# Adafruit_T-Cobbler_Plus-ADC.net
KiCad netlist of a schematic drawn in EAGLE
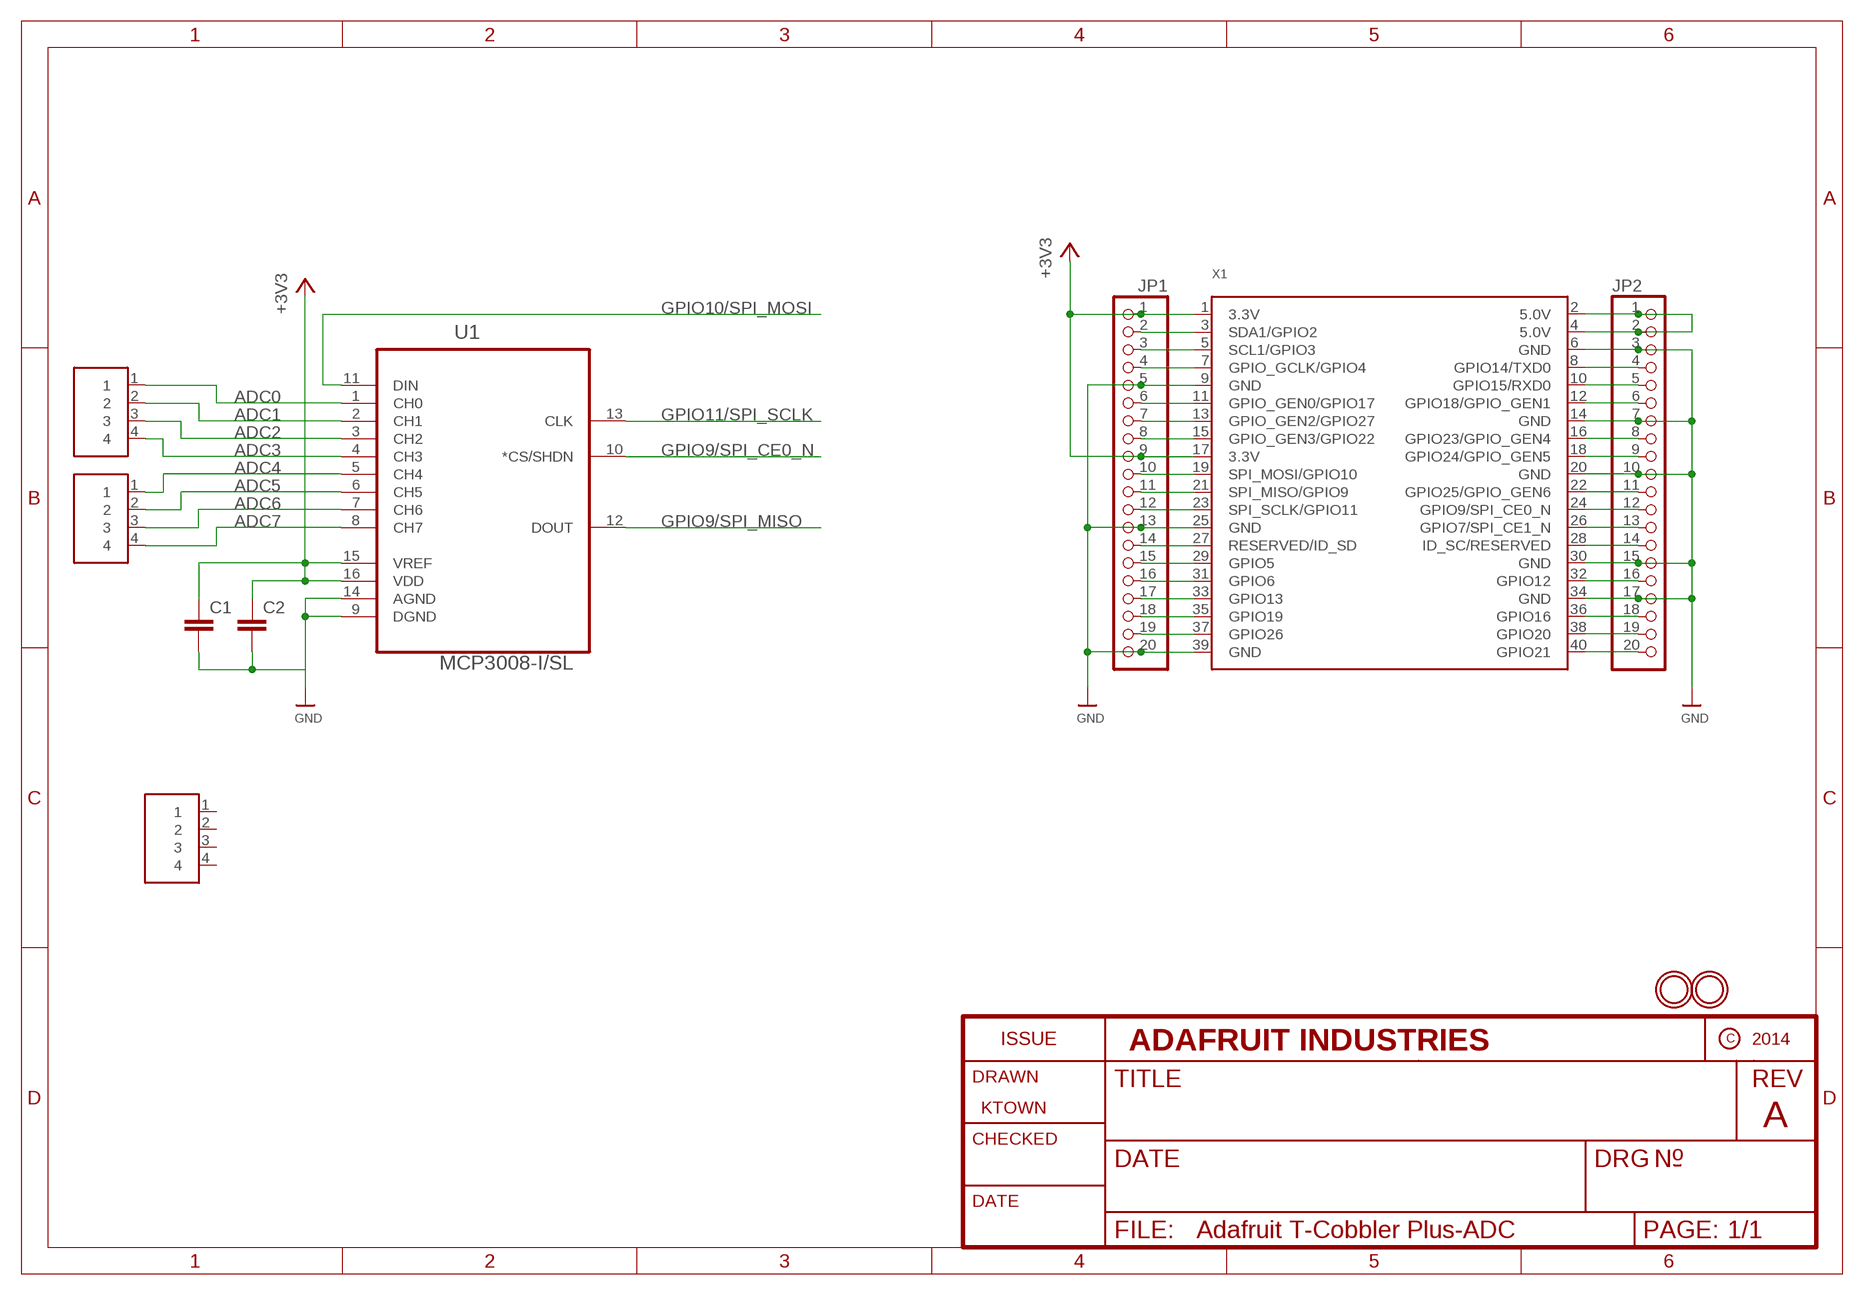
[diagram p0: schematic, sheet 1]

(export (version "E")
  (design (tool "Eeschema 10.0.6"))
  (components
    (comp (ref "C1")
      (value "C-EUC0805")
      (footprint "eagle-import:C0805")
      (libsource (lib "eagle-import") (part "C-EUC0805"))
    )
    (comp (ref "C2")
      (value "C-EUC0805")
      (footprint "eagle-import:C0805")
      (libsource (lib "eagle-import") (part "C-EUC0805"))
    )
    (comp (ref "JP1")
      (value "HEADER-1X20ROUND")
      (footprint "eagle-import:1X20_ROUND")
      (libsource (lib "eagle-import") (part "HEADER-1X20ROUND"))
    )
    (comp (ref "JP2")
      (value "HEADER-1X20ROUND")
      (footprint "eagle-import:1X20_ROUND")
      (libsource (lib "eagle-import") (part "HEADER-1X20ROUND"))
    )
    (comp (ref "U$1")
      (value "1X4THM")
      (footprint "eagle-import:1X4")
      (libsource (lib "eagle-import") (part "1X4THM"))
    )
    (comp (ref "U$2")
      (value "MOUNTINGHOLE2.5_THICK")
      (footprint "eagle-import:MOUNTINGHOLE_2.5_PLATED_THICK")
      (libsource (lib "eagle-import") (part "MOUNTINGHOLE2.5_THICK"))
    )
    (comp (ref "U$4")
      (value "MOUNTINGHOLE2.5_THICK")
      (footprint "eagle-import:MOUNTINGHOLE_2.5_PLATED_THICK")
      (libsource (lib "eagle-import") (part "MOUNTINGHOLE2.5_THICK"))
    )
    (comp (ref "U$9")
      (value "1X4THM")
      (footprint "eagle-import:1X4")
      (libsource (lib "eagle-import") (part "1X4THM"))
    )
    (comp (ref "U$10")
      (value "1X4THM")
      (footprint "eagle-import:1X4")
      (libsource (lib "eagle-import") (part "1X4THM"))
    )
    (comp (ref "U1")
      (value "MCP3008-I/SL")
      (footprint "eagle-import:SOIC127P600X175-16N")
      (libsource (lib "eagle-import") (part "MCP3008-I/SL"))
    )
    (comp (ref "X1")
      (value "RASPBERRYPI_B+_IDC")
      (footprint "eagle-import:RASPBERRYPI_B+_IDC")
      (libsource (lib "eagle-import") (part "RASPBERRYPI_B+_IDC"))
    )
  )
  (nets
    (net (code "1") (name "+3V3") (class "Default")
      (node (ref "C1") (pin "1") (pinfunction "1_1") (pintype "passive"))
      (node (ref "C2") (pin "1") (pinfunction "1_1") (pintype "passive"))
      (node (ref "JP1") (pin "1") (pinfunction "1_1") (pintype "passive"))
      (node (ref "JP1") (pin "9") (pinfunction "9_9") (pintype "passive"))
      (node (ref "U1") (pin "15") (pinfunction "VREF_15") (pintype "input"))
      (node (ref "U1") (pin "16") (pinfunction "VDD_16") (pintype "power_in"))
      (node (ref "X1") (pin "1") (pinfunction "3.3V_1") (pintype "power_in"))
      (node (ref "X1") (pin "17") (pinfunction "3.3V_17") (pintype "power_in"))
    )
    (net (code "2") (name "/ADC0") (class "Default")
      (node (ref "U$9") (pin "1") (pinfunction "1_1") (pintype "bidirectional"))
      (node (ref "U1") (pin "1") (pinfunction "CH0_1") (pintype "input"))
    )
    (net (code "3") (name "/ADC1") (class "Default")
      (node (ref "U$9") (pin "2") (pinfunction "2_2") (pintype "bidirectional"))
      (node (ref "U1") (pin "2") (pinfunction "CH1_2") (pintype "input"))
    )
    (net (code "4") (name "/ADC2") (class "Default")
      (node (ref "U$9") (pin "3") (pinfunction "3_3") (pintype "bidirectional"))
      (node (ref "U1") (pin "3") (pinfunction "CH2_3") (pintype "input"))
    )
    (net (code "5") (name "/ADC3") (class "Default")
      (node (ref "U$9") (pin "4") (pinfunction "4_4") (pintype "bidirectional"))
      (node (ref "U1") (pin "4") (pinfunction "CH3_4") (pintype "input"))
    )
    (net (code "6") (name "/ADC4") (class "Default")
      (node (ref "U$10") (pin "1") (pinfunction "1_1") (pintype "bidirectional"))
      (node (ref "U1") (pin "5") (pinfunction "CH4_5") (pintype "input"))
    )
    (net (code "7") (name "/ADC5") (class "Default")
      (node (ref "U$10") (pin "2") (pinfunction "2_2") (pintype "bidirectional"))
      (node (ref "U1") (pin "6") (pinfunction "CH5_6") (pintype "input"))
    )
    (net (code "8") (name "/ADC6") (class "Default")
      (node (ref "U$10") (pin "3") (pinfunction "3_3") (pintype "bidirectional"))
      (node (ref "U1") (pin "7") (pinfunction "CH6_7") (pintype "input"))
    )
    (net (code "9") (name "/ADC7") (class "Default")
      (node (ref "U$10") (pin "4") (pinfunction "4_4") (pintype "bidirectional"))
      (node (ref "U1") (pin "8") (pinfunction "CH7_8") (pintype "input"))
    )
    (net (code "10") (name "/GPIO9{slash}SPI_CE0_N") (class "Default")
      (node (ref "JP2") (pin "12") (pinfunction "12_12") (pintype "passive"))
      (node (ref "U1") (pin "10") (pinfunction "*CS/SHDN_10") (pintype "input"))
      (node (ref "X1") (pin "24") (pinfunction "GPIO9/SPI_CE0_N_24") (pintype "bidirectional"))
    )
    (net (code "11") (name "/GPIO9{slash}SPI_MISO") (class "Default")
      (node (ref "JP1") (pin "11") (pinfunction "11_11") (pintype "passive"))
      (node (ref "U1") (pin "12") (pinfunction "DOUT_12") (pintype "output"))
      (node (ref "X1") (pin "21") (pinfunction "SPI_MISO/GPIO9_21") (pintype "input"))
    )
    (net (code "12") (name "/GPIO10{slash}SPI_MOSI") (class "Default")
      (node (ref "JP1") (pin "10") (pinfunction "10_10") (pintype "passive"))
      (node (ref "U1") (pin "11") (pinfunction "DIN_11") (pintype "input"))
      (node (ref "X1") (pin "19") (pinfunction "SPI_MOSI/GPIO10_19") (pintype "bidirectional"))
    )
    (net (code "13") (name "/GPIO11{slash}SPI_SCLK") (class "Default")
      (node (ref "JP1") (pin "12") (pinfunction "12_12") (pintype "passive"))
      (node (ref "U1") (pin "13") (pinfunction "CLK_13") (pintype "input"))
      (node (ref "X1") (pin "23") (pinfunction "SPI_SCLK/GPIO11_23") (pintype "bidirectional"))
    )
    (net (code "14") (name "GND") (class "Default")
      (node (ref "C1") (pin "2") (pinfunction "2_2") (pintype "passive"))
      (node (ref "C2") (pin "2") (pinfunction "2_2") (pintype "passive"))
      (node (ref "JP1") (pin "13") (pinfunction "13_13") (pintype "passive"))
      (node (ref "JP1") (pin "20") (pinfunction "20_20") (pintype "passive"))
      (node (ref "JP1") (pin "5") (pinfunction "5_5") (pintype "passive"))
      (node (ref "JP2") (pin "10") (pinfunction "10_10") (pintype "passive"))
      (node (ref "JP2") (pin "15") (pinfunction "15_15") (pintype "passive"))
      (node (ref "JP2") (pin "17") (pinfunction "17_17") (pintype "passive"))
      (node (ref "JP2") (pin "3") (pinfunction "3_3") (pintype "passive"))
      (node (ref "JP2") (pin "7") (pinfunction "7_7") (pintype "passive"))
      (node (ref "U1") (pin "14") (pinfunction "AGND_14") (pintype "passive"))
      (node (ref "U1") (pin "9") (pinfunction "DGND_9") (pintype "passive"))
      (node (ref "X1") (pin "14") (pinfunction "GND_14") (pintype "power_in"))
      (node (ref "X1") (pin "20") (pinfunction "GND_20") (pintype "power_in"))
      (node (ref "X1") (pin "25") (pinfunction "GND_25") (pintype "power_in"))
      (node (ref "X1") (pin "30") (pinfunction "GND_30") (pintype "power_in"))
      (node (ref "X1") (pin "34") (pinfunction "GND_34") (pintype "power_in"))
      (node (ref "X1") (pin "39") (pinfunction "GND_39") (pintype "power_in"))
      (node (ref "X1") (pin "6") (pinfunction "GND_6") (pintype "power_in"))
      (node (ref "X1") (pin "9") (pinfunction "GND_9") (pintype "power_in"))
    )
    (net (code "15") (name "Net-(JP2-Pad1)") (class "Default")
      (node (ref "JP2") (pin "1") (pinfunction "1_1") (pintype "passive"))
      (node (ref "JP2") (pin "2") (pinfunction "2_2") (pintype "passive"))
      (node (ref "X1") (pin "2") (pinfunction "5.0V_2") (pintype "power_in"))
      (node (ref "X1") (pin "4") (pinfunction "5.0V_4") (pintype "power_in"))
    )
    (net (code "16") (name "Net-(X1-GPIO5)") (class "Default")
      (node (ref "JP1") (pin "15") (pinfunction "15_15") (pintype "passive"))
      (node (ref "X1") (pin "29") (pinfunction "GPIO5_29") (pintype "bidirectional"))
    )
    (net (code "17") (name "Net-(X1-GPIO6)") (class "Default")
      (node (ref "JP1") (pin "16") (pinfunction "16_16") (pintype "passive"))
      (node (ref "X1") (pin "31") (pinfunction "GPIO6_31") (pintype "bidirectional"))
    )
    (net (code "18") (name "Net-(X1-GPIO7{slash}SPI_CE1_N)") (class "Default")
      (node (ref "JP2") (pin "13") (pinfunction "13_13") (pintype "passive"))
      (node (ref "X1") (pin "26") (pinfunction "GPIO7/SPI_CE1_N_26") (pintype "bidirectional"))
    )
    (net (code "19") (name "Net-(X1-GPIO12)") (class "Default")
      (node (ref "JP2") (pin "16") (pinfunction "16_16") (pintype "passive"))
      (node (ref "X1") (pin "32") (pinfunction "GPIO12_32") (pintype "bidirectional"))
    )
    (net (code "20") (name "Net-(X1-GPIO13)") (class "Default")
      (node (ref "JP1") (pin "17") (pinfunction "17_17") (pintype "passive"))
      (node (ref "X1") (pin "33") (pinfunction "GPIO13_33") (pintype "bidirectional"))
    )
    (net (code "21") (name "Net-(X1-GPIO14{slash}TXD0)") (class "Default")
      (node (ref "JP2") (pin "4") (pinfunction "4_4") (pintype "passive"))
      (node (ref "X1") (pin "8") (pinfunction "GPIO14/TXD0_8") (pintype "bidirectional"))
    )
    (net (code "22") (name "Net-(X1-GPIO15{slash}RXD0)") (class "Default")
      (node (ref "JP2") (pin "5") (pinfunction "5_5") (pintype "passive"))
      (node (ref "X1") (pin "10") (pinfunction "GPIO15/RXD0_10") (pintype "bidirectional"))
    )
    (net (code "23") (name "Net-(X1-GPIO16)") (class "Default")
      (node (ref "JP2") (pin "18") (pinfunction "18_18") (pintype "passive"))
      (node (ref "X1") (pin "36") (pinfunction "GPIO16_36") (pintype "bidirectional"))
    )
    (net (code "24") (name "Net-(X1-GPIO18{slash}GPIO_GEN1)") (class "Default")
      (node (ref "JP2") (pin "6") (pinfunction "6_6") (pintype "passive"))
      (node (ref "X1") (pin "12") (pinfunction "GPIO18/GPIO_GEN1_12") (pintype "bidirectional"))
    )
    (net (code "25") (name "Net-(X1-GPIO19)") (class "Default")
      (node (ref "JP1") (pin "18") (pinfunction "18_18") (pintype "passive"))
      (node (ref "X1") (pin "35") (pinfunction "GPIO19_35") (pintype "bidirectional"))
    )
    (net (code "26") (name "Net-(X1-GPIO20)") (class "Default")
      (node (ref "JP2") (pin "19") (pinfunction "19_19") (pintype "passive"))
      (node (ref "X1") (pin "38") (pinfunction "GPIO20_38") (pintype "bidirectional"))
    )
    (net (code "27") (name "Net-(X1-GPIO21)") (class "Default")
      (node (ref "JP2") (pin "20") (pinfunction "20_20") (pintype "passive"))
      (node (ref "X1") (pin "40") (pinfunction "GPIO21_40") (pintype "bidirectional"))
    )
    (net (code "28") (name "Net-(X1-GPIO23{slash}GPIO_GEN4)") (class "Default")
      (node (ref "JP2") (pin "8") (pinfunction "8_8") (pintype "passive"))
      (node (ref "X1") (pin "16") (pinfunction "GPIO23/GPIO_GEN4_16") (pintype "bidirectional"))
    )
    (net (code "29") (name "Net-(X1-GPIO24{slash}GPIO_GEN5)") (class "Default")
      (node (ref "JP2") (pin "9") (pinfunction "9_9") (pintype "passive"))
      (node (ref "X1") (pin "18") (pinfunction "GPIO24/GPIO_GEN5_18") (pintype "bidirectional"))
    )
    (net (code "30") (name "Net-(X1-GPIO25{slash}GPIO_GEN6)") (class "Default")
      (node (ref "JP2") (pin "11") (pinfunction "11_11") (pintype "passive"))
      (node (ref "X1") (pin "22") (pinfunction "GPIO25/GPIO_GEN6_22") (pintype "bidirectional"))
    )
    (net (code "31") (name "Net-(X1-GPIO26)") (class "Default")
      (node (ref "JP1") (pin "19") (pinfunction "19_19") (pintype "passive"))
      (node (ref "X1") (pin "37") (pinfunction "GPIO26_37") (pintype "bidirectional"))
    )
    (net (code "32") (name "Net-(X1-GPIO_GCLK{slash}GPIO4)") (class "Default")
      (node (ref "JP1") (pin "4") (pinfunction "4_4") (pintype "passive"))
      (node (ref "X1") (pin "7") (pinfunction "GPIO_GCLK/GPIO4_7") (pintype "bidirectional"))
    )
    (net (code "33") (name "Net-(X1-GPIO_GEN0{slash}GPIO17)") (class "Default")
      (node (ref "JP1") (pin "6") (pinfunction "6_6") (pintype "passive"))
      (node (ref "X1") (pin "11") (pinfunction "GPIO_GEN0/GPIO17_11") (pintype "bidirectional"))
    )
    (net (code "34") (name "Net-(X1-GPIO_GEN2{slash}GPIO27)") (class "Default")
      (node (ref "JP1") (pin "7") (pinfunction "7_7") (pintype "passive"))
      (node (ref "X1") (pin "13") (pinfunction "GPIO_GEN2/GPIO27_13") (pintype "bidirectional"))
    )
    (net (code "35") (name "Net-(X1-GPIO_GEN3{slash}GPIO22)") (class "Default")
      (node (ref "JP1") (pin "8") (pinfunction "8_8") (pintype "passive"))
      (node (ref "X1") (pin "15") (pinfunction "GPIO_GEN3/GPIO22_15") (pintype "bidirectional"))
    )
    (net (code "36") (name "Net-(X1-ID_SC{slash}RESERVED)") (class "Default")
      (node (ref "JP2") (pin "14") (pinfunction "14_14") (pintype "passive"))
      (node (ref "X1") (pin "28") (pinfunction "ID_SC/RESERVED_28") (pintype "bidirectional"))
    )
    (net (code "37") (name "Net-(X1-RESERVED{slash}ID_SD)") (class "Default")
      (node (ref "JP1") (pin "14") (pinfunction "14_14") (pintype "passive"))
      (node (ref "X1") (pin "27") (pinfunction "RESERVED/ID_SD_27") (pintype "bidirectional"))
    )
    (net (code "38") (name "Net-(X1-SCL1{slash}GPIO3)") (class "Default")
      (node (ref "JP1") (pin "3") (pinfunction "3_3") (pintype "passive"))
      (node (ref "X1") (pin "5") (pinfunction "SCL1/GPIO3_5") (pintype "bidirectional"))
    )
    (net (code "39") (name "Net-(X1-SDA1{slash}GPIO2)") (class "Default")
      (node (ref "JP1") (pin "2") (pinfunction "2_2") (pintype "passive"))
      (node (ref "X1") (pin "3") (pinfunction "SDA1/GPIO2_3") (pintype "bidirectional"))
    )
    (net (code "40") (name "unconnected-(U$1-Pad1)") (class "Default")
      (node (ref "U$1") (pin "1") (pinfunction "1_1") (pintype "bidirectional"))
    )
    (net (code "41") (name "unconnected-(U$1-Pad2)") (class "Default")
      (node (ref "U$1") (pin "2") (pinfunction "2_2") (pintype "bidirectional"))
    )
    (net (code "42") (name "unconnected-(U$1-Pad3)") (class "Default")
      (node (ref "U$1") (pin "3") (pinfunction "3_3") (pintype "bidirectional"))
    )
    (net (code "43") (name "unconnected-(U$1-Pad4)") (class "Default")
      (node (ref "U$1") (pin "4") (pinfunction "4_4") (pintype "bidirectional"))
    )
  )
)
